# 250100020129x-HW-V2_1.net
KiCad netlist of a schematic drawn in EAGLE
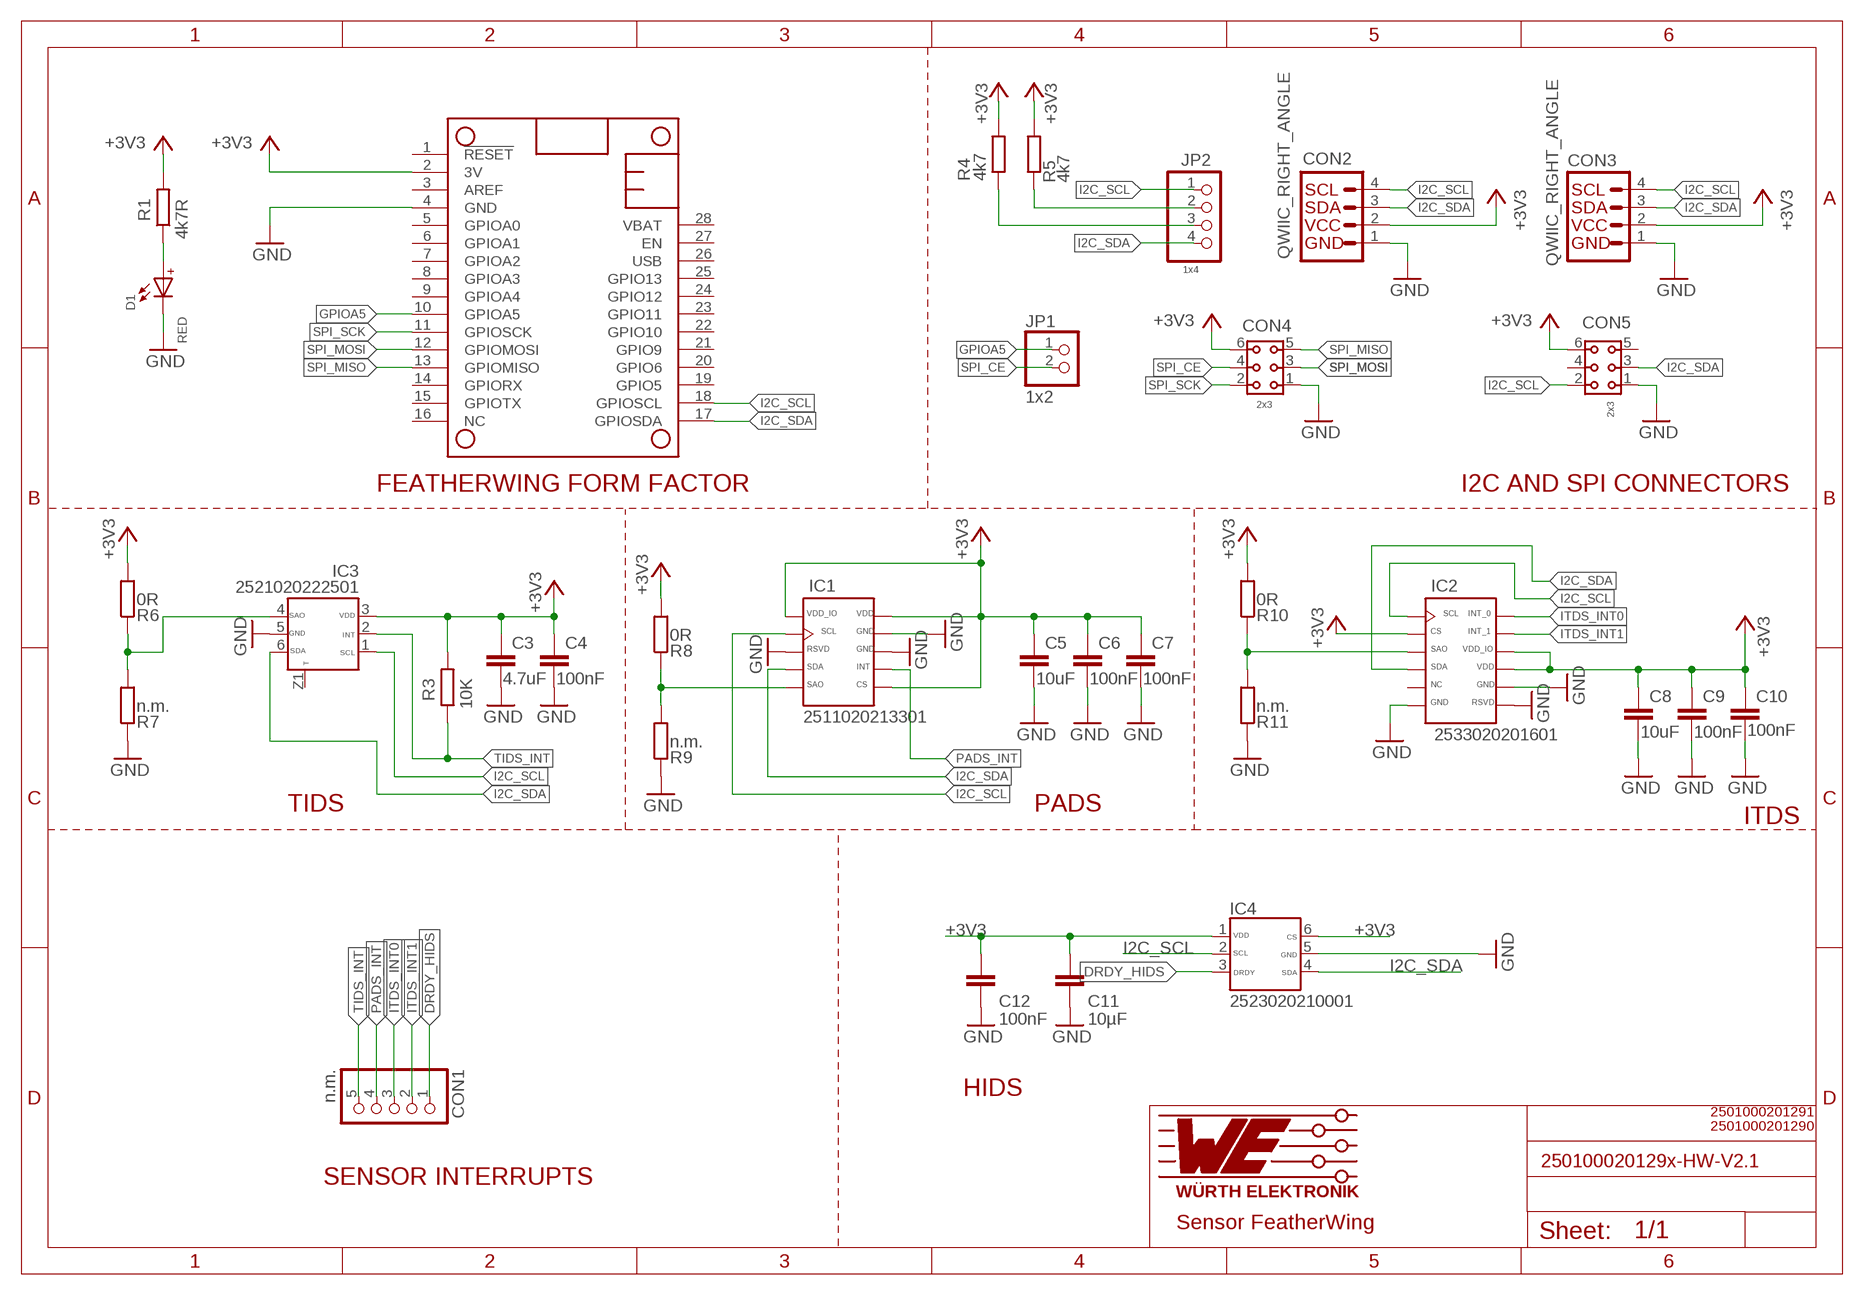
[diagram p0: schematic, sheet 1]

(export (version "E")
  (design (tool "Eeschema 10.0.6"))
  (components
    (comp (ref "C3")
      (value "4.7uF")
      (footprint "eagle-import:C0402_IPC")
      (fields (field (name "MANUFACTURER") "Murata"))
      (libsource (lib "eagle-import") (part "C0402_IPC4,7UF"))
    )
    (comp (ref "C4")
      (value "100nF")
      (footprint "eagle-import:C0402_IPC")
      (fields (field (name "MANUFACTURER") "Yageo"))
      (libsource (lib "eagle-import") (part "C0402_IPC100NF"))
    )
    (comp (ref "C5")
      (value "10uF")
      (footprint "eagle-import:C0402_IPC")
      (fields (field (name "MANUFACTURER") "Murata"))
      (libsource (lib "eagle-import") (part "C0402_IPC10UF"))
    )
    (comp (ref "C6")
      (value "100nF")
      (footprint "eagle-import:C0402_IPC")
      (fields (field (name "MANUFACTURER") "Yageo"))
      (libsource (lib "eagle-import") (part "C0402_IPC100NF"))
    )
    (comp (ref "C7")
      (value "100nF")
      (footprint "eagle-import:C0402_IPC")
      (fields (field (name "MANUFACTURER") "Yageo"))
      (libsource (lib "eagle-import") (part "C0402_IPC100NF"))
    )
    (comp (ref "C8")
      (value "10uF")
      (footprint "eagle-import:C0402_IPC")
      (fields (field (name "MANUFACTURER") "Murata"))
      (libsource (lib "eagle-import") (part "C0402_IPC10UF"))
    )
    (comp (ref "C9")
      (value "100nF")
      (footprint "eagle-import:C0402_IPC")
      (fields (field (name "MANUFACTURER") "Yageo"))
      (libsource (lib "eagle-import") (part "C0402_IPC100NF"))
    )
    (comp (ref "C10")
      (value "100nF")
      (footprint "eagle-import:C0402_IPC")
      (fields (field (name "MANUFACTURER") "Yageo"))
      (libsource (lib "eagle-import") (part "C0402_IPC100NF"))
    )
    (comp (ref "C11")
      (value "10µF")
      (footprint "eagle-import:C0402_IPC")
      (fields (field (name "MANUFACTURER") "Murata"))
      (libsource (lib "eagle-import") (part "C0402_IPC10UF"))
    )
    (comp (ref "C12")
      (value "100nF")
      (footprint "eagle-import:C0402_IPC")
      (fields (field (name "MANUFACTURER") "Yageo"))
      (libsource (lib "eagle-import") (part "C0402_IPC100NF"))
    )
    (comp (ref "CON1")
      (value "n.m.")
      (footprint "eagle-import:1X05_R")
      (fields (field (name "MANUFACTURER") "Würth Elektronik"))
      (libsource (lib "eagle-import") (part "PINHD-1X5/R"))
    )
    (comp (ref "CON2")
      (value "QWIIC_RIGHT_ANGLE")
      (footprint "eagle-import:JST04_1MM_RA")
      (fields (field (name "MANUFACTURER") "JST"))
      (libsource (lib "eagle-import") (part "QWIIC_CONNECTORJS-1MM"))
    )
    (comp (ref "CON3")
      (value "QWIIC_RIGHT_ANGLE")
      (footprint "eagle-import:JST04_1MM_RA")
      (fields (field (name "MANUFACTURER") "JST"))
      (libsource (lib "eagle-import") (part "QWIIC_CONNECTORJS-1MM"))
    )
    (comp (ref "CON4")
      (value "2x3")
      (footprint "eagle-import:613006243121")
      (fields (field (name "MANUFACTURER") "Würth Elektronik") (field (name "COMMENT") "Stick out of PCB"))
      (libsource (lib "eagle-import") (part "6130XX243121_613006243121"))
    )
    (comp (ref "CON5")
      (value "2x3")
      (footprint "eagle-import:613006243121")
      (fields (field (name "MANUFACTURER") "Würth Elektronik") (field (name "COMMENT") "Stick out of PCB"))
      (libsource (lib "eagle-import") (part "6130XX243121_613006243121"))
    )
    (comp (ref "D1")
      (value "RED")
      (footprint "eagle-import:WL-SMSW_1204_A")
      (fields (field (name "MANUFACTURER") "Würth Elektronik"))
      (libsource (lib "eagle-import") (part "WL-SMSW_1204_155124VS73200"))
    )
    (comp (ref "IC1")
      (value "2511020213301")
      (footprint "eagle-import:WSEN-PADS_2511020213301")
      (fields (field (name "MANUFACTURER") "Würth Elektronik"))
      (libsource (lib "eagle-import") (part "WSEN-PADS_2511020213301"))
    )
    (comp (ref "IC2")
      (value "2533020201601")
      (footprint "eagle-import:WSEN-ITDS_2533020201601")
      (fields (field (name "MANUFACTURER") "Würth Elektronik"))
      (libsource (lib "eagle-import") (part "WSEN-ITDS_2533020201601"))
    )
    (comp (ref "IC3")
      (value "2521020222501")
      (footprint "eagle-import:WSEN-TIDS_2521020222501")
      (fields (field (name "MANUFACTURER") "Würth Elektronik"))
      (libsource (lib "eagle-import") (part "WSEN-TIDS_2521020222501"))
    )
    (comp (ref "IC4")
      (value "2523020210001")
      (footprint "eagle-import:WSEN-HIDS_0202")
      (fields (field (name "MANUFACTURER") "Wurth Elektronik"))
      (libsource (lib "eagle-import") (part "WSEN-HIDS"))
    )
    (comp (ref "JP1")
      (value "1x2")
      (footprint "eagle-import:1X02_R")
      (fields (field (name "MANUFACTURER") "Würth Elektronik"))
      (libsource (lib "eagle-import") (part "PINHD-1X2/R"))
    )
    (comp (ref "JP2")
      (value "1x4")
      (footprint "eagle-import:1X04_R")
      (fields (field (name "COMMENT") "2xJumper, 1-2, 3-4") (field (name "MANUFACTURER") "Würth Elektronik"))
      (libsource (lib "eagle-import") (part "PINHD-1X4/R"))
    )
    (comp (ref "MS1")
      (value "FEATHERWING")
      (footprint "eagle-import:FEATHERWING")
      (fields
        (field (name "COMMENT") "header: 1 x 12 & 1 x 16, stackup, pins clean")
        (field (name "MANUFACTURER") "Adafruit")
      )
      (libsource (lib "eagle-import") (part "FEATHERWING"))
    )
    (comp (ref "R1")
      (value "4k7R")
      (footprint "eagle-import:R0402_IPC")
      (fields (field (name "MANUFACTURER") "Yageo"))
      (libsource (lib "eagle-import") (part "R0402_IPC4K7"))
    )
    (comp (ref "R3")
      (value "10K")
      (footprint "eagle-import:R0402_IPC")
      (fields (field (name "MANUFACTURER") "Yageo"))
      (libsource (lib "eagle-import") (part "R0402_IPC10KR"))
    )
    (comp (ref "R4")
      (value "4k7")
      (footprint "eagle-import:R0402_IPC")
      (fields (field (name "MANUFACTURER") "Yageo"))
      (libsource (lib "eagle-import") (part "R0402_IPC4K7"))
    )
    (comp (ref "R5")
      (value "4k7")
      (footprint "eagle-import:R0402_IPC")
      (fields (field (name "MANUFACTURER") "Yageo"))
      (libsource (lib "eagle-import") (part "R0402_IPC4K7"))
    )
    (comp (ref "R6")
      (value "0R")
      (footprint "eagle-import:R0402_IPC")
      (fields (field (name "MANUFACTURER") "Yageo"))
      (libsource (lib "eagle-import") (part "R0402_IPC0R"))
    )
    (comp (ref "R7")
      (value "n.m.")
      (footprint "eagle-import:R0402_IPC")
      (fields (field (name "MANUFACTURER") "Yageo"))
      (libsource (lib "eagle-import") (part "R0402_IPC"))
    )
    (comp (ref "R8")
      (value "0R")
      (footprint "eagle-import:R0402_IPC")
      (fields (field (name "MANUFACTURER") "Yageo"))
      (libsource (lib "eagle-import") (part "R0402_IPC0R"))
    )
    (comp (ref "R9")
      (value "n.m.")
      (footprint "eagle-import:R0402_IPC")
      (fields (field (name "MANUFACTURER") "Yageo"))
      (libsource (lib "eagle-import") (part "R0402_IPC"))
    )
    (comp (ref "R10")
      (value "0R")
      (footprint "eagle-import:R0402_IPC")
      (fields (field (name "MANUFACTURER") "Yageo"))
      (libsource (lib "eagle-import") (part "R0402_IPC0R"))
    )
    (comp (ref "R11")
      (value "n.m.")
      (footprint "eagle-import:R0402_IPC")
      (fields (field (name "MANUFACTURER") "Yageo"))
      (libsource (lib "eagle-import") (part "R0402_IPC"))
    )
  )
  (nets
    (net (code "1") (name "+3V3") (class "Default")
      (node (ref "C10") (pin "1") (pinfunction "1_1") (pintype "passive"))
      (node (ref "C11") (pin "2") (pinfunction "2_2") (pintype "passive"))
      (node (ref "C12") (pin "2") (pinfunction "2_2") (pintype "passive"))
      (node (ref "C3") (pin "1") (pinfunction "1_1") (pintype "passive"))
      (node (ref "C4") (pin "1") (pinfunction "1_1") (pintype "passive"))
      (node (ref "C5") (pin "1") (pinfunction "1_1") (pintype "passive"))
      (node (ref "C6") (pin "1") (pinfunction "1_1") (pintype "passive"))
      (node (ref "C7") (pin "1") (pinfunction "1_1") (pintype "passive"))
      (node (ref "C8") (pin "1") (pinfunction "1_1") (pintype "passive"))
      (node (ref "C9") (pin "1") (pinfunction "1_1") (pintype "passive"))
      (node (ref "CON2") (pin "2") (pinfunction "2_2") (pintype "power_in"))
      (node (ref "CON3") (pin "2") (pinfunction "2_2") (pintype "power_in"))
      (node (ref "CON4") (pin "6") (pinfunction "6_6") (pintype "passive"))
      (node (ref "CON5") (pin "6") (pinfunction "6_6") (pintype "passive"))
      (node (ref "IC1") (pin "1") (pinfunction "VDD_IO_1") (pintype "power_in"))
      (node (ref "IC1") (pin "10") (pinfunction "VDD_10") (pintype "power_in"))
      (node (ref "IC1") (pin "6") (pinfunction "CS_6") (pintype "input"))
      (node (ref "IC2") (pin "10") (pinfunction "VDD_IO_10") (pintype "power_in"))
      (node (ref "IC2") (pin "2") (pinfunction "CS_2") (pintype "input"))
      (node (ref "IC2") (pin "9") (pinfunction "VDD_9") (pintype "power_in"))
      (node (ref "IC3") (pin "3") (pinfunction "VDD_3") (pintype "power_in"))
      (node (ref "IC4") (pin "1") (pinfunction "VDD_1") (pintype "power_in"))
      (node (ref "IC4") (pin "6") (pinfunction "CS_6") (pintype "passive"))
      (node (ref "MS1") (pin "2") (pinfunction "3V_2") (pintype "power_in"))
      (node (ref "R1") (pin "2") (pinfunction "2_2") (pintype "passive"))
      (node (ref "R10") (pin "2") (pinfunction "2_2") (pintype "passive"))
      (node (ref "R3") (pin "2") (pinfunction "2_2") (pintype "passive"))
      (node (ref "R4") (pin "2") (pinfunction "2_2") (pintype "passive"))
      (node (ref "R5") (pin "2") (pinfunction "2_2") (pintype "passive"))
      (node (ref "R6") (pin "2") (pinfunction "2_2") (pintype "passive"))
      (node (ref "R8") (pin "2") (pinfunction "2_2") (pintype "passive"))
    )
    (net (code "2") (name "/USB") (class "Default")
      (node (ref "MS1") (pin "26") (pinfunction "USB_26") (pintype "power_in"))
    )
    (net (code "3") (name "/VBAT") (class "Default")
      (node (ref "MS1") (pin "28") (pinfunction "VBAT_28") (pintype "power_in"))
    )
    (net (code "4") (name "DRDY_HIDS") (class "Default")
      (node (ref "CON1") (pin "1") (pinfunction "1_1") (pintype "passive"))
      (node (ref "IC4") (pin "3") (pinfunction "DRDY_3") (pintype "output"))
    )
    (net (code "5") (name "GND") (class "Default")
      (node (ref "C10") (pin "2") (pinfunction "2_2") (pintype "passive"))
      (node (ref "C11") (pin "1") (pinfunction "1_1") (pintype "passive"))
      (node (ref "C12") (pin "1") (pinfunction "1_1") (pintype "passive"))
      (node (ref "C3") (pin "2") (pinfunction "2_2") (pintype "passive"))
      (node (ref "C4") (pin "2") (pinfunction "2_2") (pintype "passive"))
      (node (ref "C5") (pin "2") (pinfunction "2_2") (pintype "passive"))
      (node (ref "C6") (pin "2") (pinfunction "2_2") (pintype "passive"))
      (node (ref "C7") (pin "2") (pinfunction "2_2") (pintype "passive"))
      (node (ref "C8") (pin "2") (pinfunction "2_2") (pintype "passive"))
      (node (ref "C9") (pin "2") (pinfunction "2_2") (pintype "passive"))
      (node (ref "CON2") (pin "1") (pinfunction "1_1") (pintype "power_in"))
      (node (ref "CON3") (pin "1") (pinfunction "1_1") (pintype "power_in"))
      (node (ref "CON4") (pin "1") (pinfunction "1_1") (pintype "passive"))
      (node (ref "CON5") (pin "1") (pinfunction "1_1") (pintype "passive"))
      (node (ref "D1") (pin "1") (pinfunction "-_1") (pintype "passive"))
      (node (ref "IC1") (pin "3") (pinfunction "RSVD_3") (pintype "bidirectional"))
      (node (ref "IC1") (pin "8") (pinfunction "GND_8") (pintype "power_in"))
      (node (ref "IC1") (pin "9") (pinfunction "GND_9") (pintype "power_in"))
      (node (ref "IC2") (pin "6") (pinfunction "GND_6") (pintype "power_in"))
      (node (ref "IC2") (pin "7") (pinfunction "RSVD_7") (pintype "bidirectional"))
      (node (ref "IC2") (pin "8") (pinfunction "GND_8") (pintype "power_in"))
      (node (ref "IC3") (pin "5") (pinfunction "GND_5") (pintype "power_in"))
      (node (ref "IC4") (pin "5") (pinfunction "GND_5") (pintype "power_in"))
      (node (ref "MS1") (pin "4") (pinfunction "GND_4") (pintype "power_in"))
      (node (ref "R11") (pin "1") (pinfunction "1_1") (pintype "passive"))
      (node (ref "R7") (pin "1") (pinfunction "1_1") (pintype "passive"))
      (node (ref "R9") (pin "1") (pinfunction "1_1") (pintype "passive"))
    )
    (net (code "6") (name "GPIOA5") (class "Default")
      (node (ref "JP1") (pin "1") (pinfunction "1_1") (pintype "passive"))
      (node (ref "MS1") (pin "10") (pinfunction "GPIOA5_10") (pintype "bidirectional"))
    )
    (net (code "7") (name "I2C_SCL") (class "Default")
      (node (ref "CON2") (pin "4") (pinfunction "4_4") (pintype "passive"))
      (node (ref "CON3") (pin "4") (pinfunction "4_4") (pintype "passive"))
      (node (ref "CON5") (pin "2") (pinfunction "2_2") (pintype "passive"))
      (node (ref "IC1") (pin "2") (pinfunction "SCL_2") (pintype "input"))
      (node (ref "IC2") (pin "1") (pinfunction "SCL_1") (pintype "input"))
      (node (ref "IC3") (pin "1") (pinfunction "SCL_1") (pintype "bidirectional"))
      (node (ref "IC4") (pin "2") (pinfunction "SCL_2") (pintype "bidirectional"))
      (node (ref "JP2") (pin "1") (pinfunction "1_1") (pintype "passive"))
      (node (ref "MS1") (pin "18") (pinfunction "GPIOSCL_18") (pintype "bidirectional"))
    )
    (net (code "8") (name "I2C_SDA") (class "Default")
      (node (ref "CON2") (pin "3") (pinfunction "3_3") (pintype "passive"))
      (node (ref "CON3") (pin "3") (pinfunction "3_3") (pintype "passive"))
      (node (ref "CON5") (pin "3") (pinfunction "3_3") (pintype "passive"))
      (node (ref "IC1") (pin "4") (pinfunction "SDA_4") (pintype "bidirectional"))
      (node (ref "IC2") (pin "4") (pinfunction "SDA_4") (pintype "bidirectional"))
      (node (ref "IC3") (pin "6") (pinfunction "SDA_6") (pintype "bidirectional"))
      (node (ref "IC4") (pin "4") (pinfunction "SDA_4") (pintype "bidirectional"))
      (node (ref "JP2") (pin "4") (pinfunction "4_4") (pintype "passive"))
      (node (ref "MS1") (pin "17") (pinfunction "GPIOSDA_17") (pintype "bidirectional"))
    )
    (net (code "9") (name "ITDS_INT0") (class "Default")
      (node (ref "CON1") (pin "3") (pinfunction "3_3") (pintype "passive"))
      (node (ref "IC2") (pin "12") (pinfunction "INT_0_12") (pintype "output"))
    )
    (net (code "10") (name "ITDS_INT1") (class "Default")
      (node (ref "CON1") (pin "2") (pinfunction "2_2") (pintype "passive"))
      (node (ref "IC2") (pin "11") (pinfunction "INT_1_11") (pintype "bidirectional"))
    )
    (net (code "11") (name "Net-(D1-+)") (class "Default")
      (node (ref "D1") (pin "2") (pinfunction "+_2") (pintype "passive"))
      (node (ref "R1") (pin "1") (pinfunction "1_1") (pintype "passive"))
    )
    (net (code "12") (name "Net-(IC1-SAO)") (class "Default")
      (node (ref "IC1") (pin "5") (pinfunction "SAO_5") (pintype "bidirectional"))
      (node (ref "R8") (pin "1") (pinfunction "1_1") (pintype "passive"))
      (node (ref "R9") (pin "2") (pinfunction "2_2") (pintype "passive"))
    )
    (net (code "13") (name "Net-(IC2-SAO)") (class "Default")
      (node (ref "IC2") (pin "3") (pinfunction "SAO_3") (pintype "bidirectional"))
      (node (ref "R10") (pin "1") (pinfunction "1_1") (pintype "passive"))
      (node (ref "R11") (pin "2") (pinfunction "2_2") (pintype "passive"))
    )
    (net (code "14") (name "Net-(IC3-SAO)") (class "Default")
      (node (ref "IC3") (pin "4") (pinfunction "SAO_4") (pintype "bidirectional"))
      (node (ref "R6") (pin "1") (pinfunction "1_1") (pintype "passive"))
      (node (ref "R7") (pin "2") (pinfunction "2_2") (pintype "passive"))
    )
    (net (code "15") (name "Net-(JP2-Pad2)") (class "Default")
      (node (ref "JP2") (pin "2") (pinfunction "2_2") (pintype "passive"))
      (node (ref "R5") (pin "1") (pinfunction "1_1") (pintype "passive"))
    )
    (net (code "16") (name "Net-(JP2-Pad3)") (class "Default")
      (node (ref "JP2") (pin "3") (pinfunction "3_3") (pintype "passive"))
      (node (ref "R4") (pin "1") (pinfunction "1_1") (pintype "passive"))
    )
    (net (code "17") (name "PADS_INT") (class "Default")
      (node (ref "CON1") (pin "4") (pinfunction "4_4") (pintype "passive"))
      (node (ref "IC1") (pin "7") (pinfunction "INT_7") (pintype "output"))
    )
    (net (code "18") (name "SPI_CE") (class "Default")
      (node (ref "CON4") (pin "4") (pinfunction "4_4") (pintype "passive"))
      (node (ref "JP1") (pin "2") (pinfunction "2_2") (pintype "passive"))
    )
    (net (code "19") (name "SPI_MISO") (class "Default")
      (node (ref "CON4") (pin "5") (pinfunction "5_5") (pintype "passive"))
      (node (ref "MS1") (pin "13") (pinfunction "GPIOMISO_13") (pintype "bidirectional"))
    )
    (net (code "20") (name "SPI_MOSI") (class "Default")
      (node (ref "CON4") (pin "3") (pinfunction "3_3") (pintype "passive"))
      (node (ref "MS1") (pin "12") (pinfunction "GPIOMOSI_12") (pintype "bidirectional"))
    )
    (net (code "21") (name "SPI_SCK") (class "Default")
      (node (ref "CON4") (pin "2") (pinfunction "2_2") (pintype "passive"))
      (node (ref "MS1") (pin "11") (pinfunction "GPIOSCK_11") (pintype "bidirectional"))
    )
    (net (code "22") (name "TIDS_INT") (class "Default")
      (node (ref "CON1") (pin "5") (pinfunction "5_5") (pintype "passive"))
      (node (ref "IC3") (pin "2") (pinfunction "INT_2") (pintype "bidirectional"))
      (node (ref "R3") (pin "1") (pinfunction "1_1") (pintype "passive"))
    )
    (net (code "23") (name "unconnected-(CON5-Pad4)") (class "Default")
      (node (ref "CON5") (pin "4") (pinfunction "4_4") (pintype "passive"))
    )
    (net (code "24") (name "unconnected-(CON5-Pad5)") (class "Default")
      (node (ref "CON5") (pin "5") (pinfunction "5_5") (pintype "passive"))
    )
    (net (code "25") (name "unconnected-(IC2-NC-Pad5)") (class "Default")
      (node (ref "IC2") (pin "5") (pinfunction "NC_5") (pintype "no_connect"))
    )
    (net (code "26") (name "unconnected-(IC3-P$1-PadZ1)") (class "Default")
      (node (ref "IC3") (pin "Z1") (pinfunction "P$1_Z1") (pintype "bidirectional"))
    )
    (net (code "27") (name "unconnected-(MS1-AREF-Pad3)") (class "Default")
      (node (ref "MS1") (pin "3") (pinfunction "AREF_3") (pintype "passive"))
    )
    (net (code "28") (name "unconnected-(MS1-EN-Pad27)") (class "Default")
      (node (ref "MS1") (pin "27") (pinfunction "EN_27") (pintype "passive"))
    )
    (net (code "29") (name "unconnected-(MS1-GPIO5-Pad19)") (class "Default")
      (node (ref "MS1") (pin "19") (pinfunction "GPIO5_19") (pintype "bidirectional"))
    )
    (net (code "30") (name "unconnected-(MS1-GPIO6-Pad20)") (class "Default")
      (node (ref "MS1") (pin "20") (pinfunction "GPIO6_20") (pintype "bidirectional"))
    )
    (net (code "31") (name "unconnected-(MS1-GPIO9-Pad21)") (class "Default")
      (node (ref "MS1") (pin "21") (pinfunction "GPIO9_21") (pintype "bidirectional"))
    )
    (net (code "32") (name "unconnected-(MS1-GPIO10-Pad22)") (class "Default")
      (node (ref "MS1") (pin "22") (pinfunction "GPIO10_22") (pintype "bidirectional"))
    )
    (net (code "33") (name "unconnected-(MS1-GPIO11-Pad23)") (class "Default")
      (node (ref "MS1") (pin "23") (pinfunction "GPIO11_23") (pintype "bidirectional"))
    )
    (net (code "34") (name "unconnected-(MS1-GPIO12-Pad24)") (class "Default")
      (node (ref "MS1") (pin "24") (pinfunction "GPIO12_24") (pintype "bidirectional"))
    )
    (net (code "35") (name "unconnected-(MS1-GPIO13-Pad25)") (class "Default")
      (node (ref "MS1") (pin "25") (pinfunction "GPIO13_25") (pintype "bidirectional"))
    )
    (net (code "36") (name "unconnected-(MS1-GPIOA0-Pad5)") (class "Default")
      (node (ref "MS1") (pin "5") (pinfunction "GPIOA0_5") (pintype "bidirectional"))
    )
    (net (code "37") (name "unconnected-(MS1-GPIOA1-Pad6)") (class "Default")
      (node (ref "MS1") (pin "6") (pinfunction "GPIOA1_6") (pintype "bidirectional"))
    )
    (net (code "38") (name "unconnected-(MS1-GPIOA2-Pad7)") (class "Default")
      (node (ref "MS1") (pin "7") (pinfunction "GPIOA2_7") (pintype "bidirectional"))
    )
    (net (code "39") (name "unconnected-(MS1-GPIOA3-Pad8)") (class "Default")
      (node (ref "MS1") (pin "8") (pinfunction "GPIOA3_8") (pintype "bidirectional"))
    )
    (net (code "40") (name "unconnected-(MS1-GPIOA4-Pad9)") (class "Default")
      (node (ref "MS1") (pin "9") (pinfunction "GPIOA4_9") (pintype "bidirectional"))
    )
    (net (code "41") (name "unconnected-(MS1-GPIORX-Pad14)") (class "Default")
      (node (ref "MS1") (pin "14") (pinfunction "GPIORX_14") (pintype "bidirectional"))
    )
    (net (code "42") (name "unconnected-(MS1-GPIOTX-Pad15)") (class "Default")
      (node (ref "MS1") (pin "15") (pinfunction "GPIOTX_15") (pintype "bidirectional"))
    )
    (net (code "43") (name "unconnected-(MS1-NC-Pad16)") (class "Default")
      (node (ref "MS1") (pin "16") (pinfunction "NC_16") (pintype "passive"))
    )
    (net (code "44") (name "unconnected-(MS1-~{RESET}-Pad1)") (class "Default")
      (node (ref "MS1") (pin "1") (pinfunction "~{RESET}_1") (pintype "input"))
    )
  )
)
